# ver060_LPF.net
KiCad netlist of a schematic drawn in Altium Designer
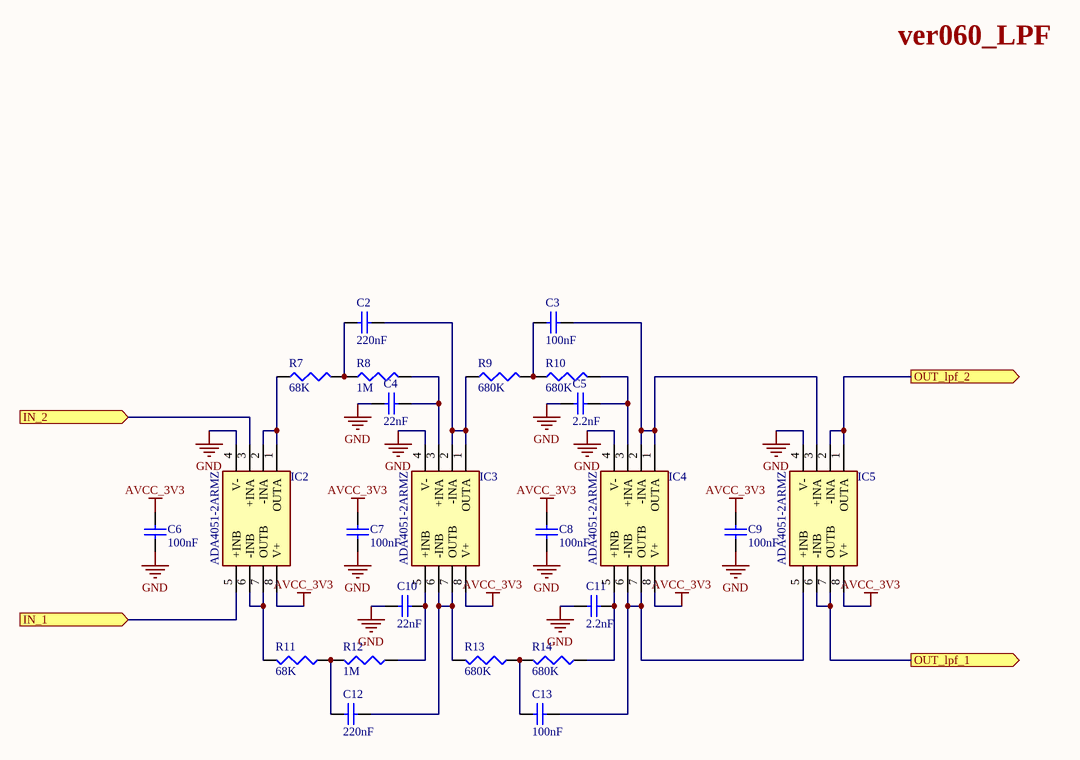
[diagram p0: ver060_LPF.SchDoc]

(export (version "E")
  (design (tool "Eeschema 10.0.6"))
  (components
    (comp (ref "C2")
      (value "220nF")
      (footprint "1608[0603]")
      (description "Capacitor (Semiconductor SIM Model)")
      (fields (field (name "Comment") "Cap Semi") (field (name "PUBLISHER") "Altium Limited"))
      (libsource (lib "Miscellaneous Devices") (part "Cap Semi"))
    )
    (comp (ref "C3")
      (value "100nF")
      (footprint "1608[0603]")
      (description "Capacitor (Semiconductor SIM Model)")
      (fields (field (name "Comment") "Cap Semi") (field (name "PUBLISHER") "Altium Limited"))
      (libsource (lib "Miscellaneous Devices") (part "Cap Semi"))
    )
    (comp (ref "C4")
      (value "22nF")
      (footprint "1608[0603]")
      (description "Capacitor (Semiconductor SIM Model)")
      (fields (field (name "Comment") "Cap Semi") (field (name "PUBLISHER") "Altium Limited"))
      (libsource (lib "Miscellaneous Devices") (part "Cap Semi"))
    )
    (comp (ref "C5")
      (value "2.2nF")
      (footprint "1608[0603]")
      (description "Capacitor (Semiconductor SIM Model)")
      (fields (field (name "Comment") "Cap Semi") (field (name "PUBLISHER") "Altium Limited"))
      (libsource (lib "Miscellaneous Devices") (part "Cap Semi"))
    )
    (comp (ref "C6")
      (value "100nF")
      (footprint "1608[0603]")
      (description "Capacitor (Semiconductor SIM Model)")
      (fields (field (name "Comment") "Cap Semi") (field (name "PUBLISHER") "Altium Limited"))
      (libsource (lib "Miscellaneous Devices") (part "Cap Semi"))
    )
    (comp (ref "C7")
      (value "100nF")
      (footprint "1608[0603]")
      (description "Capacitor (Semiconductor SIM Model)")
      (fields (field (name "Comment") "Cap Semi") (field (name "PUBLISHER") "Altium Limited"))
      (libsource (lib "Miscellaneous Devices") (part "Cap Semi"))
    )
    (comp (ref "C8")
      (value "100nF")
      (footprint "1608[0603]")
      (description "Capacitor (Semiconductor SIM Model)")
      (fields (field (name "Comment") "Cap Semi") (field (name "PUBLISHER") "Altium Limited"))
      (libsource (lib "Miscellaneous Devices") (part "Cap Semi"))
    )
    (comp (ref "C9")
      (value "100nF")
      (footprint "1608[0603]")
      (description "Capacitor (Semiconductor SIM Model)")
      (fields (field (name "Comment") "Cap Semi") (field (name "PUBLISHER") "Altium Limited"))
      (libsource (lib "Miscellaneous Devices") (part "Cap Semi"))
    )
    (comp (ref "C10")
      (value "22nF")
      (footprint "1608[0603]")
      (description "Capacitor (Semiconductor SIM Model)")
      (fields (field (name "Comment") "Cap Semi") (field (name "PUBLISHER") "Altium Limited"))
      (libsource (lib "Miscellaneous Devices") (part "Cap Semi"))
    )
    (comp (ref "C11")
      (value "2.2nF")
      (footprint "1608[0603]")
      (description "Capacitor (Semiconductor SIM Model)")
      (fields (field (name "Comment") "Cap Semi") (field (name "PUBLISHER") "Altium Limited"))
      (libsource (lib "Miscellaneous Devices") (part "Cap Semi"))
    )
    (comp (ref "C12")
      (value "220nF")
      (footprint "1608[0603]")
      (description "Capacitor (Semiconductor SIM Model)")
      (fields (field (name "Comment") "Cap Semi") (field (name "PUBLISHER") "Altium Limited"))
      (libsource (lib "Miscellaneous Devices") (part "Cap Semi"))
    )
    (comp (ref "C13")
      (value "100nF")
      (footprint "1608[0603]")
      (description "Capacitor (Semiconductor SIM Model)")
      (fields (field (name "Comment") "Cap Semi") (field (name "PUBLISHER") "Altium Limited"))
      (libsource (lib "Miscellaneous Devices") (part "Cap Semi"))
    )
    (comp (ref "IC2")
      (value "ADA4051-2ARMZ")
      (footprint "nanowire:SOP65P490X110-8N")
      (description "Integrated Circuit")
      (fields (field (name "MOUSER PART NUMBER") "584-ADA4051-2ARMZ"))
      (libsource (lib "nanowire") (part "ADA4051-2ARMZ"))
    )
    (comp (ref "IC3")
      (value "ADA4051-2ARMZ")
      (footprint "nanowire:SOP65P490X110-8N")
      (description "Integrated Circuit")
      (fields (field (name "MOUSER PART NUMBER") "584-ADA4051-2ARMZ"))
      (libsource (lib "nanowire") (part "ADA4051-2ARMZ"))
    )
    (comp (ref "IC4")
      (value "ADA4051-2ARMZ")
      (footprint "nanowire:SOP65P490X110-8N")
      (description "Integrated Circuit")
      (fields (field (name "MOUSER PART NUMBER") "584-ADA4051-2ARMZ"))
      (libsource (lib "nanowire") (part "ADA4051-2ARMZ"))
    )
    (comp (ref "IC5")
      (value "ADA4051-2ARMZ")
      (footprint "nanowire:SOP65P490X110-8N")
      (description "Integrated Circuit")
      (fields (field (name "MOUSER PART NUMBER") "584-ADA4051-2ARMZ"))
      (libsource (lib "nanowire") (part "ADA4051-2ARMZ"))
    )
    (comp (ref "R7")
      (value "68K")
      (footprint "J1-0603")
      (description "Resistor")
      (fields (field (name "Comment") "Res3") (field (name "PUBLISHER") "Altium Limited"))
      (libsource (lib "Miscellaneous Devices") (part "Res3"))
    )
    (comp (ref "R8")
      (value "1M")
      (footprint "J1-0603")
      (description "Resistor")
      (fields (field (name "Comment") "Res3") (field (name "PUBLISHER") "Altium Limited"))
      (libsource (lib "Miscellaneous Devices") (part "Res3"))
    )
    (comp (ref "R9")
      (value "680K")
      (footprint "J1-0603")
      (description "Resistor")
      (fields (field (name "Comment") "Res3") (field (name "PUBLISHER") "Altium Limited"))
      (libsource (lib "Miscellaneous Devices") (part "Res3"))
    )
    (comp (ref "R10")
      (value "680K")
      (footprint "J1-0603")
      (description "Resistor")
      (fields (field (name "Comment") "Res3") (field (name "PUBLISHER") "Altium Limited"))
      (libsource (lib "Miscellaneous Devices") (part "Res3"))
    )
    (comp (ref "R11")
      (value "68K")
      (footprint "J1-0603")
      (description "Resistor")
      (fields (field (name "Comment") "Res3") (field (name "PUBLISHER") "Altium Limited"))
      (libsource (lib "Miscellaneous Devices") (part "Res3"))
    )
    (comp (ref "R12")
      (value "1M")
      (footprint "J1-0603")
      (description "Resistor")
      (fields (field (name "Comment") "Res3") (field (name "PUBLISHER") "Altium Limited"))
      (libsource (lib "Miscellaneous Devices") (part "Res3"))
    )
    (comp (ref "R13")
      (value "680K")
      (footprint "J1-0603")
      (description "Resistor")
      (fields (field (name "Comment") "Res3") (field (name "PUBLISHER") "Altium Limited"))
      (libsource (lib "Miscellaneous Devices") (part "Res3"))
    )
    (comp (ref "R14")
      (value "680K")
      (footprint "J1-0603")
      (description "Resistor")
      (fields (field (name "Comment") "Res3") (field (name "PUBLISHER") "Altium Limited"))
      (libsource (lib "Miscellaneous Devices") (part "Res3"))
    )
  )
  (nets
    (net (code "1") (name "/IN_1") (class "Default")
      (node (ref "IC2") (pin "5") (pinfunction "+INB_5") (pintype "passive"))
    )
    (net (code "2") (name "/IN_2") (class "Default")
      (node (ref "IC2") (pin "3") (pinfunction "+INA_3") (pintype "passive"))
    )
    (net (code "3") (name "/OUT_lpf_1") (class "Default")
      (node (ref "IC5") (pin "6") (pinfunction "-INB_6") (pintype "passive"))
      (node (ref "IC5") (pin "7") (pinfunction "OUTB_7") (pintype "passive"))
    )
    (net (code "4") (name "/OUT_lpf_2") (class "Default")
      (node (ref "IC5") (pin "1") (pinfunction "OUTA_1") (pintype "passive"))
      (node (ref "IC5") (pin "2") (pinfunction "-INA_2") (pintype "passive"))
    )
    (net (code "5") (name "AVCC_3V3") (class "Default")
      (node (ref "C6") (pin "2") (pinfunction "2_2") (pintype "passive"))
      (node (ref "C7") (pin "2") (pinfunction "2_2") (pintype "passive"))
      (node (ref "C8") (pin "2") (pinfunction "2_2") (pintype "passive"))
      (node (ref "C9") (pin "2") (pinfunction "2_2") (pintype "passive"))
      (node (ref "IC2") (pin "8") (pinfunction "V+_8") (pintype "passive"))
      (node (ref "IC3") (pin "8") (pinfunction "V+_8") (pintype "passive"))
      (node (ref "IC4") (pin "8") (pinfunction "V+_8") (pintype "passive"))
      (node (ref "IC5") (pin "8") (pinfunction "V+_8") (pintype "passive"))
    )
    (net (code "6") (name "GND") (class "Default")
      (node (ref "C10") (pin "1") (pinfunction "1_1") (pintype "passive"))
      (node (ref "C11") (pin "1") (pinfunction "1_1") (pintype "passive"))
      (node (ref "C4") (pin "1") (pinfunction "1_1") (pintype "passive"))
      (node (ref "C5") (pin "1") (pinfunction "1_1") (pintype "passive"))
      (node (ref "C6") (pin "1") (pinfunction "1_1") (pintype "passive"))
      (node (ref "C7") (pin "1") (pinfunction "1_1") (pintype "passive"))
      (node (ref "C8") (pin "1") (pinfunction "1_1") (pintype "passive"))
      (node (ref "C9") (pin "1") (pinfunction "1_1") (pintype "passive"))
      (node (ref "IC2") (pin "4") (pinfunction "V-_4") (pintype "passive"))
      (node (ref "IC3") (pin "4") (pinfunction "V-_4") (pintype "passive"))
      (node (ref "IC4") (pin "4") (pinfunction "V-_4") (pintype "passive"))
      (node (ref "IC5") (pin "4") (pinfunction "V-_4") (pintype "passive"))
    )
    (net (code "7") (name "Net-(C2-Pad1)") (class "Default")
      (node (ref "C2") (pin "1") (pinfunction "1_1") (pintype "passive"))
      (node (ref "R7") (pin "1") (pinfunction "1_1") (pintype "passive"))
      (node (ref "R8") (pin "2") (pinfunction "2_2") (pintype "passive"))
    )
    (net (code "8") (name "Net-(C3-Pad1)") (class "Default")
      (node (ref "C3") (pin "1") (pinfunction "1_1") (pintype "passive"))
      (node (ref "R10") (pin "2") (pinfunction "2_2") (pintype "passive"))
      (node (ref "R9") (pin "1") (pinfunction "1_1") (pintype "passive"))
    )
    (net (code "9") (name "Net-(C12-Pad1)") (class "Default")
      (node (ref "C12") (pin "1") (pinfunction "1_1") (pintype "passive"))
      (node (ref "R11") (pin "1") (pinfunction "1_1") (pintype "passive"))
      (node (ref "R12") (pin "2") (pinfunction "2_2") (pintype "passive"))
    )
    (net (code "10") (name "Net-(C13-Pad1)") (class "Default")
      (node (ref "C13") (pin "1") (pinfunction "1_1") (pintype "passive"))
      (node (ref "R13") (pin "1") (pinfunction "1_1") (pintype "passive"))
      (node (ref "R14") (pin "2") (pinfunction "2_2") (pintype "passive"))
    )
    (net (code "11") (name "Net-(IC2--INA)") (class "Default")
      (node (ref "IC2") (pin "1") (pinfunction "OUTA_1") (pintype "passive"))
      (node (ref "IC2") (pin "2") (pinfunction "-INA_2") (pintype "passive"))
      (node (ref "R7") (pin "2") (pinfunction "2_2") (pintype "passive"))
    )
    (net (code "12") (name "Net-(IC2--INB)") (class "Default")
      (node (ref "IC2") (pin "6") (pinfunction "-INB_6") (pintype "passive"))
      (node (ref "IC2") (pin "7") (pinfunction "OUTB_7") (pintype "passive"))
      (node (ref "R11") (pin "2") (pinfunction "2_2") (pintype "passive"))
    )
    (net (code "13") (name "Net-(IC3-+INA)") (class "Default")
      (node (ref "C4") (pin "2") (pinfunction "2_2") (pintype "passive"))
      (node (ref "IC3") (pin "3") (pinfunction "+INA_3") (pintype "passive"))
      (node (ref "R8") (pin "1") (pinfunction "1_1") (pintype "passive"))
    )
    (net (code "14") (name "Net-(IC3-+INB)") (class "Default")
      (node (ref "C10") (pin "2") (pinfunction "2_2") (pintype "passive"))
      (node (ref "IC3") (pin "5") (pinfunction "+INB_5") (pintype "passive"))
      (node (ref "R12") (pin "1") (pinfunction "1_1") (pintype "passive"))
    )
    (net (code "15") (name "Net-(IC3--INA)") (class "Default")
      (node (ref "C2") (pin "2") (pinfunction "2_2") (pintype "passive"))
      (node (ref "IC3") (pin "1") (pinfunction "OUTA_1") (pintype "passive"))
      (node (ref "IC3") (pin "2") (pinfunction "-INA_2") (pintype "passive"))
      (node (ref "R9") (pin "2") (pinfunction "2_2") (pintype "passive"))
    )
    (net (code "16") (name "Net-(IC3--INB)") (class "Default")
      (node (ref "C12") (pin "2") (pinfunction "2_2") (pintype "passive"))
      (node (ref "IC3") (pin "6") (pinfunction "-INB_6") (pintype "passive"))
      (node (ref "IC3") (pin "7") (pinfunction "OUTB_7") (pintype "passive"))
      (node (ref "R13") (pin "2") (pinfunction "2_2") (pintype "passive"))
    )
    (net (code "17") (name "Net-(IC4-+INA)") (class "Default")
      (node (ref "C5") (pin "2") (pinfunction "2_2") (pintype "passive"))
      (node (ref "IC4") (pin "3") (pinfunction "+INA_3") (pintype "passive"))
      (node (ref "R10") (pin "1") (pinfunction "1_1") (pintype "passive"))
    )
    (net (code "18") (name "Net-(IC4-+INB)") (class "Default")
      (node (ref "C11") (pin "2") (pinfunction "2_2") (pintype "passive"))
      (node (ref "IC4") (pin "5") (pinfunction "+INB_5") (pintype "passive"))
      (node (ref "R14") (pin "1") (pinfunction "1_1") (pintype "passive"))
    )
    (net (code "19") (name "Net-(IC4--INA)") (class "Default")
      (node (ref "C3") (pin "2") (pinfunction "2_2") (pintype "passive"))
      (node (ref "IC4") (pin "1") (pinfunction "OUTA_1") (pintype "passive"))
      (node (ref "IC4") (pin "2") (pinfunction "-INA_2") (pintype "passive"))
      (node (ref "IC5") (pin "3") (pinfunction "+INA_3") (pintype "passive"))
    )
    (net (code "20") (name "Net-(IC4--INB)") (class "Default")
      (node (ref "C13") (pin "2") (pinfunction "2_2") (pintype "passive"))
      (node (ref "IC4") (pin "6") (pinfunction "-INB_6") (pintype "passive"))
      (node (ref "IC4") (pin "7") (pinfunction "OUTB_7") (pintype "passive"))
      (node (ref "IC5") (pin "5") (pinfunction "+INB_5") (pintype "passive"))
    )
  )
)
